# 0131-dcdc-3a.net
KiCad netlist of a schematic drawn in EAGLE
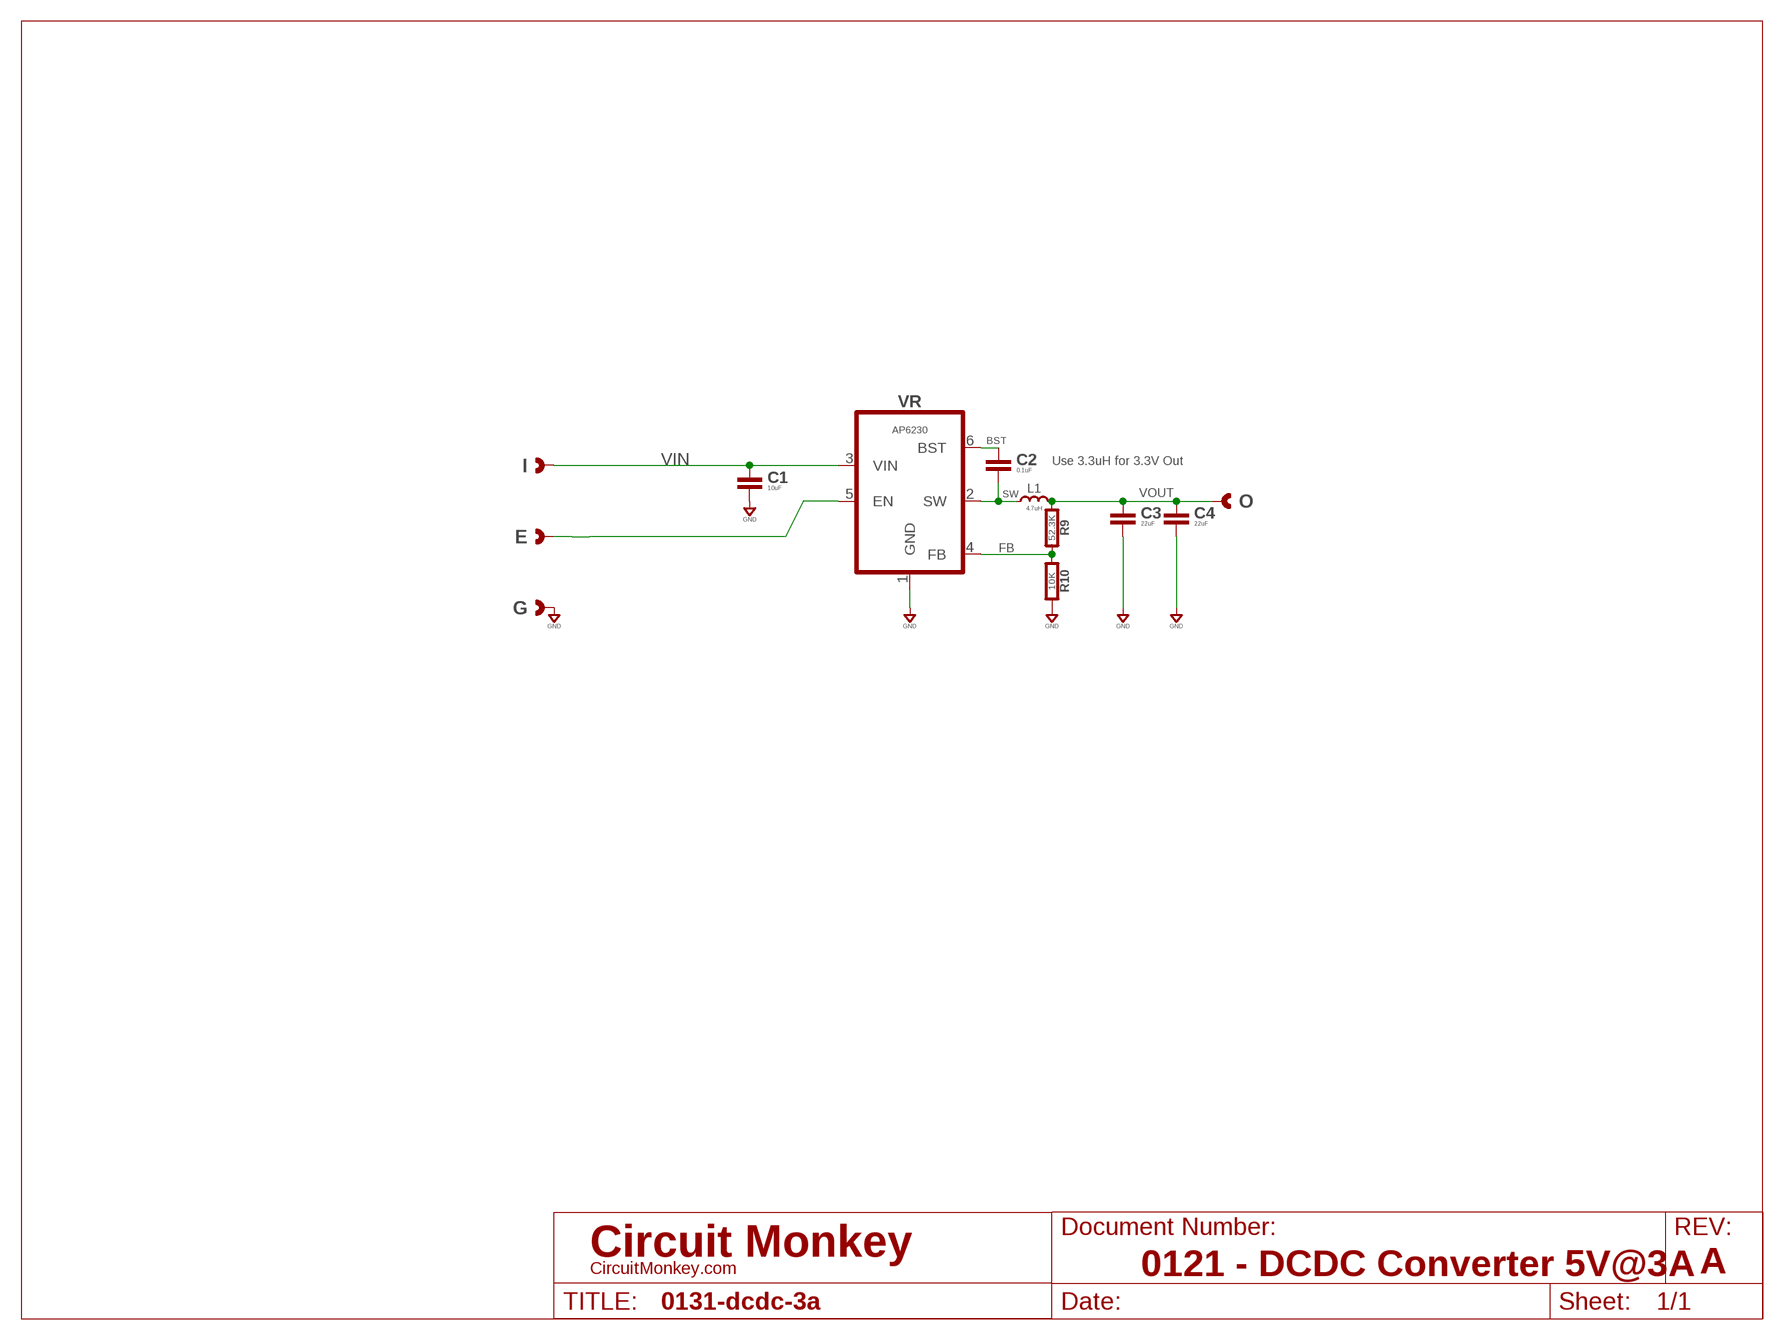
[diagram p0: schematic, sheet 1]

(export (version "E")
  (design (tool "Eeschema 10.0.6"))
  (components
    (comp (ref "C1")
      (value "10uF")
      (footprint "eagle-import:0603-CAP")
      (libsource (lib "eagle-import") (part "CAPACITOR0603"))
    )
    (comp (ref "C2")
      (value "0.1uF")
      (footprint "eagle-import:0603-CAP")
      (libsource (lib "eagle-import") (part "CAPACITOR0603"))
    )
    (comp (ref "C3")
      (value "22uF")
      (footprint "eagle-import:0603-CAP")
      (libsource (lib "eagle-import") (part "CAPACITOR0603"))
    )
    (comp (ref "C4")
      (value "22uF")
      (footprint "eagle-import:0603-CAP")
      (libsource (lib "eagle-import") (part "CAPACITOR0603"))
    )
    (comp (ref "E")
      (value "CAST-01X12.00MM")
      (footprint "eagle-import:CAST01-2.00MM")
      (libsource (lib "eagle-import") (part "CAST-01X12.00MM"))
    )
    (comp (ref "G")
      (value "CAST-01X12.00MM")
      (footprint "eagle-import:CAST01-2.00MM")
      (libsource (lib "eagle-import") (part "CAST-01X12.00MM"))
    )
    (comp (ref "I")
      (value "CAST-01X12.00MM")
      (footprint "eagle-import:CAST01-2.00MM")
      (libsource (lib "eagle-import") (part "CAST-01X12.00MM"))
    )
    (comp (ref "L1")
      (value "4.7uH")
      (footprint "eagle-import:IND-SRN5040")
      (fields
        (field (name "MFR") "Bourns")
        (field (name "MPN") "SRN5040")
        (field (name "MPN_1") "SRN5040-3R3M")
      )
      (libsource (lib "eagle-import") (part "INDUCTORSMD-05X04MM"))
    )
    (comp (ref "O")
      (value "CAST-01X12.00MM")
      (footprint "eagle-import:CAST01-2.00MM")
      (libsource (lib "eagle-import") (part "CAST-01X12.00MM"))
    )
    (comp (ref "R9")
      (value "52.3K")
      (footprint "eagle-import:0603-RES")
      (libsource (lib "eagle-import") (part "RESISTOR0603"))
    )
    (comp (ref "R10")
      (value "10K")
      (footprint "eagle-import:0603-RES")
      (libsource (lib "eagle-import") (part "RESISTOR0603"))
    )
    (comp (ref "VR")
      (value "AP6230")
      (footprint "eagle-import:TSOT26")
      (fields (field (name "MFR") "Diodes, Inc.") (field (name "MPN") "AP62300WU"))
      (libsource (lib "eagle-import") (part "BUCKAP62300-WU"))
    )
  )
  (nets
    (net (code "1") (name "/BST") (class "Default")
      (node (ref "C2") (pin "1") (pinfunction "1_1") (pintype "passive"))
      (node (ref "VR") (pin "6") (pinfunction "BST_6") (pintype "bidirectional"))
    )
    (net (code "2") (name "/FB") (class "Default")
      (node (ref "R10") (pin "1") (pinfunction "1_1") (pintype "passive"))
      (node (ref "R9") (pin "2") (pinfunction "2_2") (pintype "passive"))
      (node (ref "VR") (pin "4") (pinfunction "FB_4") (pintype "bidirectional"))
    )
    (net (code "3") (name "/SW") (class "Default")
      (node (ref "C2") (pin "2") (pinfunction "2_2") (pintype "passive"))
      (node (ref "L1") (pin "2") (pinfunction "P$2_2") (pintype "passive"))
      (node (ref "VR") (pin "2") (pinfunction "SW_2") (pintype "bidirectional"))
    )
    (net (code "4") (name "/VIN") (class "Default")
      (node (ref "C1") (pin "1") (pinfunction "1_1") (pintype "passive"))
      (node (ref "I") (pin "1") (pinfunction "1_1") (pintype "bidirectional"))
      (node (ref "I") (pin "P$1") (pinfunction "1_P$1") (pintype "bidirectional"))
      (node (ref "I") (pin "P$2") (pinfunction "1_P$2") (pintype "bidirectional"))
      (node (ref "VR") (pin "3") (pinfunction "VIN_3") (pintype "bidirectional"))
    )
    (net (code "5") (name "/VOUT") (class "Default")
      (node (ref "C3") (pin "1") (pinfunction "1_1") (pintype "passive"))
      (node (ref "C4") (pin "1") (pinfunction "1_1") (pintype "passive"))
      (node (ref "L1") (pin "1") (pinfunction "P$1_1") (pintype "passive"))
      (node (ref "O") (pin "1") (pinfunction "1_1") (pintype "bidirectional"))
      (node (ref "O") (pin "P$1") (pinfunction "1_P$1") (pintype "bidirectional"))
      (node (ref "O") (pin "P$2") (pinfunction "1_P$2") (pintype "bidirectional"))
      (node (ref "R9") (pin "1") (pinfunction "1_1") (pintype "passive"))
    )
    (net (code "6") (name "GND") (class "Default")
      (node (ref "C1") (pin "2") (pinfunction "2_2") (pintype "passive"))
      (node (ref "C3") (pin "2") (pinfunction "2_2") (pintype "passive"))
      (node (ref "C4") (pin "2") (pinfunction "2_2") (pintype "passive"))
      (node (ref "G") (pin "1") (pinfunction "1_1") (pintype "bidirectional"))
      (node (ref "G") (pin "P$1") (pinfunction "1_P$1") (pintype "bidirectional"))
      (node (ref "G") (pin "P$2") (pinfunction "1_P$2") (pintype "bidirectional"))
      (node (ref "R10") (pin "2") (pinfunction "2_2") (pintype "passive"))
      (node (ref "VR") (pin "1") (pinfunction "GND_1") (pintype "bidirectional"))
    )
    (net (code "7") (name "Net-(VR-EN)") (class "Default")
      (node (ref "E") (pin "1") (pinfunction "1_1") (pintype "bidirectional"))
      (node (ref "E") (pin "P$1") (pinfunction "1_P$1") (pintype "bidirectional"))
      (node (ref "E") (pin "P$2") (pinfunction "1_P$2") (pintype "bidirectional"))
      (node (ref "VR") (pin "5") (pinfunction "EN_5") (pintype "bidirectional"))
    )
  )
)
